# exBoard_4.net
KiCad netlist of a schematic drawn in EasyEDA Pro
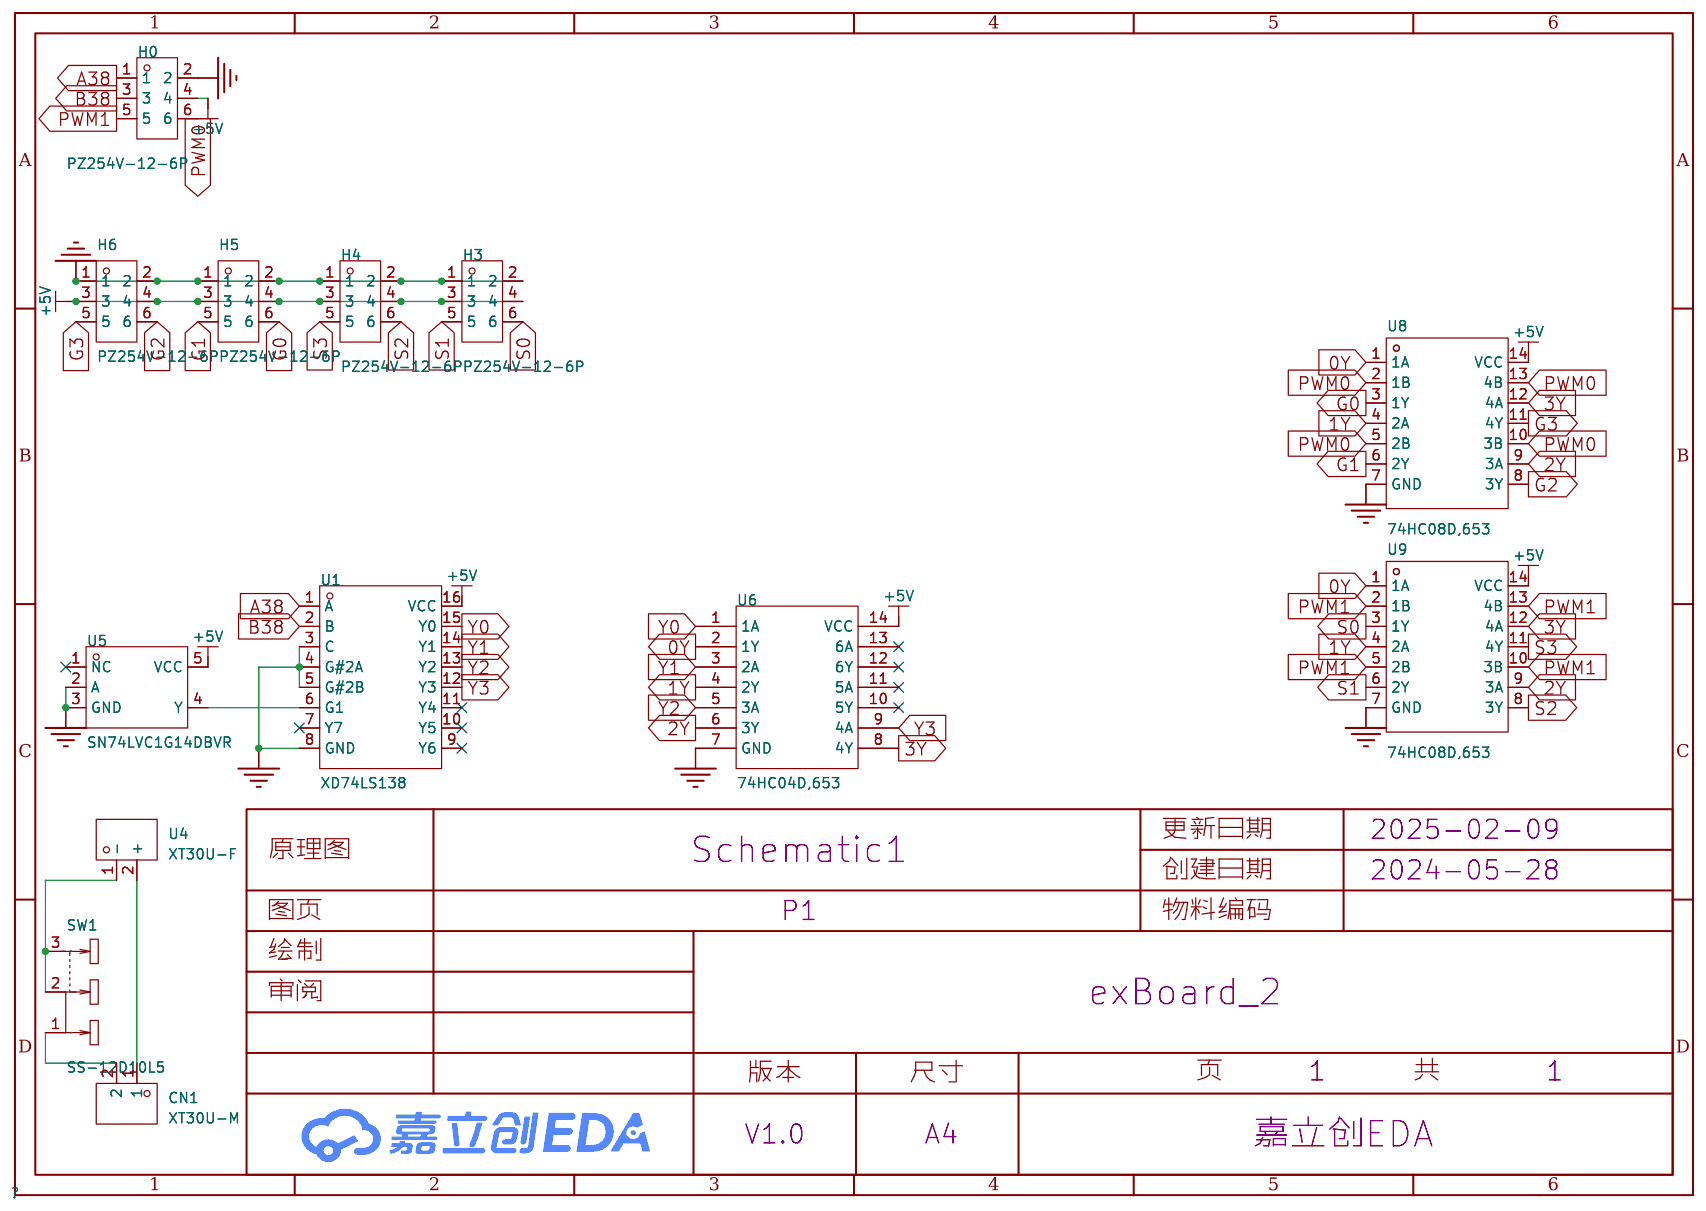
[diagram p0: schematic sheet]

(export (version "E")
  (design (tool "Eeschema 10.0.6"))
  (components
    (comp (ref "CN1")
      (value "XT30U-M")
      (footprint "easyedapro:CONN-TH_XT30U-M")
      (description "类别:-;类型1:-;")
      (fields (field (name "Manufacturer") "AMASS(艾迈斯)"))
      (libsource (lib "easyedapro") (part "XT30U-M"))
    )
    (comp (ref "H0")
      (value "PZ254V-12-6P")
      (footprint "easyedapro:HDR-TH_6P-P2.54-V-M-R2-C3-S2.54")
      (fields (field (name "Manufacturer") "XFCN(兴飞)"))
      (libsource (lib "easyedapro") (part "PZ254V-12-6P"))
    )
    (comp (ref "H3")
      (value "PZ254V-12-6P")
      (footprint "easyedapro:HDR-TH_6P-P2.54-V-M-R2-C3-S2.54")
      (fields (field (name "Manufacturer") "XFCN(兴飞)"))
      (libsource (lib "easyedapro") (part "PZ254V-12-6P"))
    )
    (comp (ref "H4")
      (value "PZ254V-12-6P")
      (footprint "easyedapro:HDR-TH_6P-P2.54-V-M-R2-C3-S2.54")
      (fields (field (name "Manufacturer") "XFCN(兴飞)"))
      (libsource (lib "easyedapro") (part "PZ254V-12-6P"))
    )
    (comp (ref "H5")
      (value "PZ254V-12-6P")
      (footprint "easyedapro:HDR-TH_6P-P2.54-V-M-R2-C3-S2.54")
      (fields (field (name "Manufacturer") "XFCN(兴飞)"))
      (libsource (lib "easyedapro") (part "PZ254V-12-6P"))
    )
    (comp (ref "H6")
      (value "PZ254V-12-6P")
      (footprint "easyedapro:HDR-TH_6P-P2.54-V-M-R2-C3-S2.54")
      (fields (field (name "Manufacturer") "XFCN(兴飞)"))
      (libsource (lib "easyedapro") (part "PZ254V-12-6P"))
    )
    (comp (ref "SW1")
      (value "SS-12D10L5")
      (footprint "easyedapro:SW-TH_SS-12D10L5")
      (description "电路结构:单刀双掷;安装方式:直插;开关颜色:黑色;额定电流(DC):3A;额定电压(DC):125V;额定电流(AC):3A;额定电压(AC):125V;机械寿命:1万次;")
      (fields (field (name "Manufacturer") "XKB Connectivity(中国星坤)"))
      (libsource (lib "easyedapro") (part "SS-12D10L5"))
    )
    (comp (ref "U1")
      (value "XD74LS138")
      (footprint "easyedapro:DIP-16_L19.8-W6.5-P2.54-LS7.6-BL")
      (description "解码器/多路解器 低电平输出电流(IOL)：8mA 高电平输出电流(IOH)：400uA 供电电源：单电源 供电电压：4.75V~5.25V 3 线路到")
      (fields (field (name "Manufacturer") "XINLUDA(信路达)"))
      (libsource (lib "easyedapro") (part "XD74LS138"))
    )
    (comp (ref "U4")
      (value "XT30U-F")
      (footprint "easyedapro:CONN-TH_XT30U-F")
      (description "类别:-;类型1:-;")
      (fields (field (name "Manufacturer") "AMASS(艾迈斯)"))
      (libsource (lib "easyedapro") (part "XT30U-F"))
    )
    (comp (ref "U5")
      (value "SN74LVC1G14DBVR")
      (footprint "easyedapro:SOT-23-5_L3.0-W1.7-P0.95-LS2.8-BR")
      (description "输入类型:施密特触发器;电源电压:1.65V~5.5V;供电电流(最大值):10uA;电路数:1;最大传播延迟(tpd):20ns@5V,15pF;")
      (fields (field (name "Manufacturer") "UMW(友台半导体)"))
      (libsource (lib "easyedapro") (part "SN74LVC1G14DBVR_C434069"))
    )
    (comp (ref "U6")
      (value "74HC04D,653")
      (footprint "easyedapro:SOIC-14_L8.7-W3.9-P1.27-LS6.0-BL")
      (description "输入类型:-;电源电压:2V~6V;供电电流(最大值):2uA;电路数:6;最大传播延迟(tpd):14ns@6V,50pF;")
      (fields (field (name "Manufacturer") "Nexperia(安世)"))
      (libsource (lib "easyedapro") (part "74HC04D,653"))
    )
    (comp (ref "U8")
      (value "74HC08D,653")
      (footprint "easyedapro:SOIC-14_L8.7-W3.9-P1.27-LS6.0-BL")
      (description "逻辑类型:与门;通道数:4;电源电压:2V~6V;静态电流(最大值):2uA;最大传播延迟:15ns@6V,50pF;")
      (fields (field (name "Manufacturer") "Nexperia(安世)"))
      (libsource (lib "easyedapro") (part "74HC08D,653"))
    )
    (comp (ref "U9")
      (value "74HC08D,653")
      (footprint "easyedapro:SOIC-14_L8.7-W3.9-P1.27-LS6.0-BL")
      (description "逻辑类型:与门;通道数:4;电源电压:2V~6V;静态电流(最大值):2uA;最大传播延迟:15ns@6V,50pF;")
      (fields (field (name "Manufacturer") "Nexperia(安世)"))
      (libsource (lib "easyedapro") (part "74HC08D,653"))
    )
  )
  (nets
    (net (code "1") (name "+5V") (class "Default")
      (node (ref "H0") (pin "4") (pinfunction "4_4") (pintype "unspecified"))
      (node (ref "H3") (pin "3") (pinfunction "3_3") (pintype "unspecified"))
      (node (ref "H3") (pin "4") (pinfunction "4_4") (pintype "unspecified"))
      (node (ref "H4") (pin "3") (pinfunction "3_3") (pintype "unspecified"))
      (node (ref "H4") (pin "4") (pinfunction "4_4") (pintype "unspecified"))
      (node (ref "H5") (pin "3") (pinfunction "3_3") (pintype "unspecified"))
      (node (ref "H5") (pin "4") (pinfunction "4_4") (pintype "unspecified"))
      (node (ref "H6") (pin "3") (pinfunction "3_3") (pintype "unspecified"))
      (node (ref "H6") (pin "4") (pinfunction "4_4") (pintype "unspecified"))
      (node (ref "U1") (pin "16") (pinfunction "VCC_16") (pintype "unspecified"))
      (node (ref "U5") (pin "5") (pinfunction "VCC_5") (pintype "unspecified"))
      (node (ref "U6") (pin "14") (pinfunction "VCC_14") (pintype "unspecified"))
      (node (ref "U8") (pin "14") (pinfunction "VCC_14") (pintype "unspecified"))
      (node (ref "U9") (pin "14") (pinfunction "VCC_14") (pintype "unspecified"))
    )
    (net (code "2") (name "0Y") (class "Default")
      (node (ref "U6") (pin "2") (pinfunction "1Y_2") (pintype "unspecified"))
      (node (ref "U8") (pin "1") (pinfunction "1A_1") (pintype "unspecified"))
      (node (ref "U9") (pin "1") (pinfunction "1A_1") (pintype "unspecified"))
    )
    (net (code "3") (name "1Y") (class "Default")
      (node (ref "U6") (pin "4") (pinfunction "2Y_4") (pintype "unspecified"))
      (node (ref "U8") (pin "4") (pinfunction "2A_4") (pintype "unspecified"))
      (node (ref "U9") (pin "4") (pinfunction "2A_4") (pintype "unspecified"))
    )
    (net (code "4") (name "2Y") (class "Default")
      (node (ref "U6") (pin "6") (pinfunction "3Y_6") (pintype "unspecified"))
      (node (ref "U8") (pin "9") (pinfunction "3A_9") (pintype "unspecified"))
      (node (ref "U9") (pin "9") (pinfunction "3A_9") (pintype "unspecified"))
    )
    (net (code "5") (name "3Y") (class "Default")
      (node (ref "U6") (pin "8") (pinfunction "4Y_8") (pintype "unspecified"))
      (node (ref "U8") (pin "12") (pinfunction "4A_12") (pintype "unspecified"))
      (node (ref "U9") (pin "12") (pinfunction "4A_12") (pintype "unspecified"))
    )
    (net (code "6") (name "A38") (class "Default")
      (node (ref "H0") (pin "1") (pinfunction "1_1") (pintype "unspecified"))
      (node (ref "U1") (pin "1") (pinfunction "A_1") (pintype "unspecified"))
    )
    (net (code "7") (name "B38") (class "Default")
      (node (ref "H0") (pin "3") (pinfunction "3_3") (pintype "unspecified"))
      (node (ref "U1") (pin "2") (pinfunction "B_2") (pintype "unspecified"))
    )
    (net (code "8") (name "G0") (class "Default")
      (node (ref "H5") (pin "6") (pinfunction "6_6") (pintype "unspecified"))
      (node (ref "U8") (pin "3") (pinfunction "1Y_3") (pintype "unspecified"))
    )
    (net (code "9") (name "G1") (class "Default")
      (node (ref "H5") (pin "5") (pinfunction "5_5") (pintype "unspecified"))
      (node (ref "U8") (pin "6") (pinfunction "2Y_6") (pintype "unspecified"))
    )
    (net (code "10") (name "G2") (class "Default")
      (node (ref "H6") (pin "6") (pinfunction "6_6") (pintype "unspecified"))
      (node (ref "U8") (pin "8") (pinfunction "3Y_8") (pintype "unspecified"))
    )
    (net (code "11") (name "G3") (class "Default")
      (node (ref "H6") (pin "5") (pinfunction "5_5") (pintype "unspecified"))
      (node (ref "U8") (pin "11") (pinfunction "4Y_11") (pintype "unspecified"))
    )
    (net (code "12") (name "GND") (class "Default")
      (node (ref "H0") (pin "2") (pinfunction "2_2") (pintype "unspecified"))
      (node (ref "H3") (pin "1") (pinfunction "1_1") (pintype "unspecified"))
      (node (ref "H3") (pin "2") (pinfunction "2_2") (pintype "unspecified"))
      (node (ref "H4") (pin "1") (pinfunction "1_1") (pintype "unspecified"))
      (node (ref "H4") (pin "2") (pinfunction "2_2") (pintype "unspecified"))
      (node (ref "H5") (pin "1") (pinfunction "1_1") (pintype "unspecified"))
      (node (ref "H5") (pin "2") (pinfunction "2_2") (pintype "unspecified"))
      (node (ref "H6") (pin "1") (pinfunction "1_1") (pintype "unspecified"))
      (node (ref "H6") (pin "2") (pinfunction "2_2") (pintype "unspecified"))
      (node (ref "U1") (pin "3") (pinfunction "C_3") (pintype "unspecified"))
      (node (ref "U1") (pin "4") (pinfunction "G#2A_4") (pintype "unspecified"))
      (node (ref "U1") (pin "5") (pinfunction "G#2B_5") (pintype "unspecified"))
      (node (ref "U1") (pin "8") (pinfunction "GND_8") (pintype "unspecified"))
      (node (ref "U5") (pin "2") (pinfunction "A_2") (pintype "unspecified"))
      (node (ref "U5") (pin "3") (pinfunction "GND_3") (pintype "unspecified"))
      (node (ref "U6") (pin "7") (pinfunction "GND_7") (pintype "unspecified"))
      (node (ref "U8") (pin "7") (pinfunction "GND_7") (pintype "unspecified"))
      (node (ref "U9") (pin "7") (pinfunction "GND_7") (pintype "unspecified"))
    )
    (net (code "13") (name "Net-(CN1-Pad2)") (class "Default")
      (node (ref "CN1") (pin "2") (pinfunction "2_2") (pintype "input"))
      (node (ref "SW1") (pin "1") (pinfunction "1_1") (pintype "unspecified"))
    )
    (net (code "14") (name "Net-(U1-G1)") (class "Default")
      (node (ref "U1") (pin "6") (pinfunction "G1_6") (pintype "unspecified"))
      (node (ref "U5") (pin "4") (pinfunction "Y_4") (pintype "unspecified"))
    )
    (net (code "15") (name "Net-(U4-+)") (class "Default")
      (node (ref "CN1") (pin "1") (pinfunction "1_1") (pintype "input"))
      (node (ref "U4") (pin "2") (pinfunction "+_2") (pintype "unspecified"))
    )
    (net (code "16") (name "Net-(U4--)") (class "Default")
      (node (ref "SW1") (pin "2") (pinfunction "2_2") (pintype "unspecified"))
      (node (ref "SW1") (pin "3") (pinfunction "3_3") (pintype "unspecified"))
      (node (ref "U4") (pin "1") (pinfunction "-_1") (pintype "unspecified"))
    )
    (net (code "17") (name "PWM0") (class "Default")
      (node (ref "H0") (pin "6") (pinfunction "6_6") (pintype "unspecified"))
      (node (ref "U8") (pin "10") (pinfunction "3B_10") (pintype "unspecified"))
      (node (ref "U8") (pin "13") (pinfunction "4B_13") (pintype "unspecified"))
      (node (ref "U8") (pin "2") (pinfunction "1B_2") (pintype "unspecified"))
      (node (ref "U8") (pin "5") (pinfunction "2B_5") (pintype "unspecified"))
    )
    (net (code "18") (name "PWM1") (class "Default")
      (node (ref "H0") (pin "5") (pinfunction "5_5") (pintype "unspecified"))
      (node (ref "U9") (pin "10") (pinfunction "3B_10") (pintype "unspecified"))
      (node (ref "U9") (pin "13") (pinfunction "4B_13") (pintype "unspecified"))
      (node (ref "U9") (pin "2") (pinfunction "1B_2") (pintype "unspecified"))
      (node (ref "U9") (pin "5") (pinfunction "2B_5") (pintype "unspecified"))
    )
    (net (code "19") (name "S0") (class "Default")
      (node (ref "H3") (pin "6") (pinfunction "6_6") (pintype "unspecified"))
      (node (ref "U9") (pin "3") (pinfunction "1Y_3") (pintype "unspecified"))
    )
    (net (code "20") (name "S1") (class "Default")
      (node (ref "H3") (pin "5") (pinfunction "5_5") (pintype "unspecified"))
      (node (ref "U9") (pin "6") (pinfunction "2Y_6") (pintype "unspecified"))
    )
    (net (code "21") (name "S2") (class "Default")
      (node (ref "H4") (pin "6") (pinfunction "6_6") (pintype "unspecified"))
      (node (ref "U9") (pin "8") (pinfunction "3Y_8") (pintype "unspecified"))
    )
    (net (code "22") (name "S3") (class "Default")
      (node (ref "H4") (pin "5") (pinfunction "5_5") (pintype "unspecified"))
      (node (ref "U9") (pin "11") (pinfunction "4Y_11") (pintype "unspecified"))
    )
    (net (code "23") (name "Y0") (class "Default")
      (node (ref "U1") (pin "15") (pinfunction "Y0_15") (pintype "unspecified"))
      (node (ref "U6") (pin "1") (pinfunction "1A_1") (pintype "unspecified"))
    )
    (net (code "24") (name "Y1") (class "Default")
      (node (ref "U1") (pin "14") (pinfunction "Y1_14") (pintype "unspecified"))
      (node (ref "U6") (pin "3") (pinfunction "2A_3") (pintype "unspecified"))
    )
    (net (code "25") (name "Y2") (class "Default")
      (node (ref "U1") (pin "13") (pinfunction "Y2_13") (pintype "unspecified"))
      (node (ref "U6") (pin "5") (pinfunction "3A_5") (pintype "unspecified"))
    )
    (net (code "26") (name "Y3") (class "Default")
      (node (ref "U1") (pin "12") (pinfunction "Y3_12") (pintype "unspecified"))
      (node (ref "U6") (pin "9") (pinfunction "4A_9") (pintype "unspecified"))
    )
    (net (code "27") (name "unconnected-(U1-Y4-Pad11)") (class "Default")
      (node (ref "U1") (pin "11") (pinfunction "Y4_11") (pintype "unspecified+no_connect"))
    )
    (net (code "28") (name "unconnected-(U1-Y5-Pad10)") (class "Default")
      (node (ref "U1") (pin "10") (pinfunction "Y5_10") (pintype "unspecified+no_connect"))
    )
    (net (code "29") (name "unconnected-(U1-Y6-Pad9)") (class "Default")
      (node (ref "U1") (pin "9") (pinfunction "Y6_9") (pintype "unspecified+no_connect"))
    )
    (net (code "30") (name "unconnected-(U1-Y7-Pad7)") (class "Default")
      (node (ref "U1") (pin "7") (pinfunction "Y7_7") (pintype "unspecified+no_connect"))
    )
    (net (code "31") (name "unconnected-(U5-NC-Pad1)") (class "Default")
      (node (ref "U5") (pin "1") (pinfunction "NC_1") (pintype "unspecified+no_connect"))
    )
    (net (code "32") (name "unconnected-(U6-5A-Pad11)") (class "Default")
      (node (ref "U6") (pin "11") (pinfunction "5A_11") (pintype "unspecified+no_connect"))
    )
    (net (code "33") (name "unconnected-(U6-5Y-Pad10)") (class "Default")
      (node (ref "U6") (pin "10") (pinfunction "5Y_10") (pintype "unspecified+no_connect"))
    )
    (net (code "34") (name "unconnected-(U6-6A-Pad13)") (class "Default")
      (node (ref "U6") (pin "13") (pinfunction "6A_13") (pintype "unspecified+no_connect"))
    )
    (net (code "35") (name "unconnected-(U6-6Y-Pad12)") (class "Default")
      (node (ref "U6") (pin "12") (pinfunction "6Y_12") (pintype "unspecified+no_connect"))
    )
  )
)
